# CAN_IF.net
KiCad netlist of a schematic drawn in Altium Designer
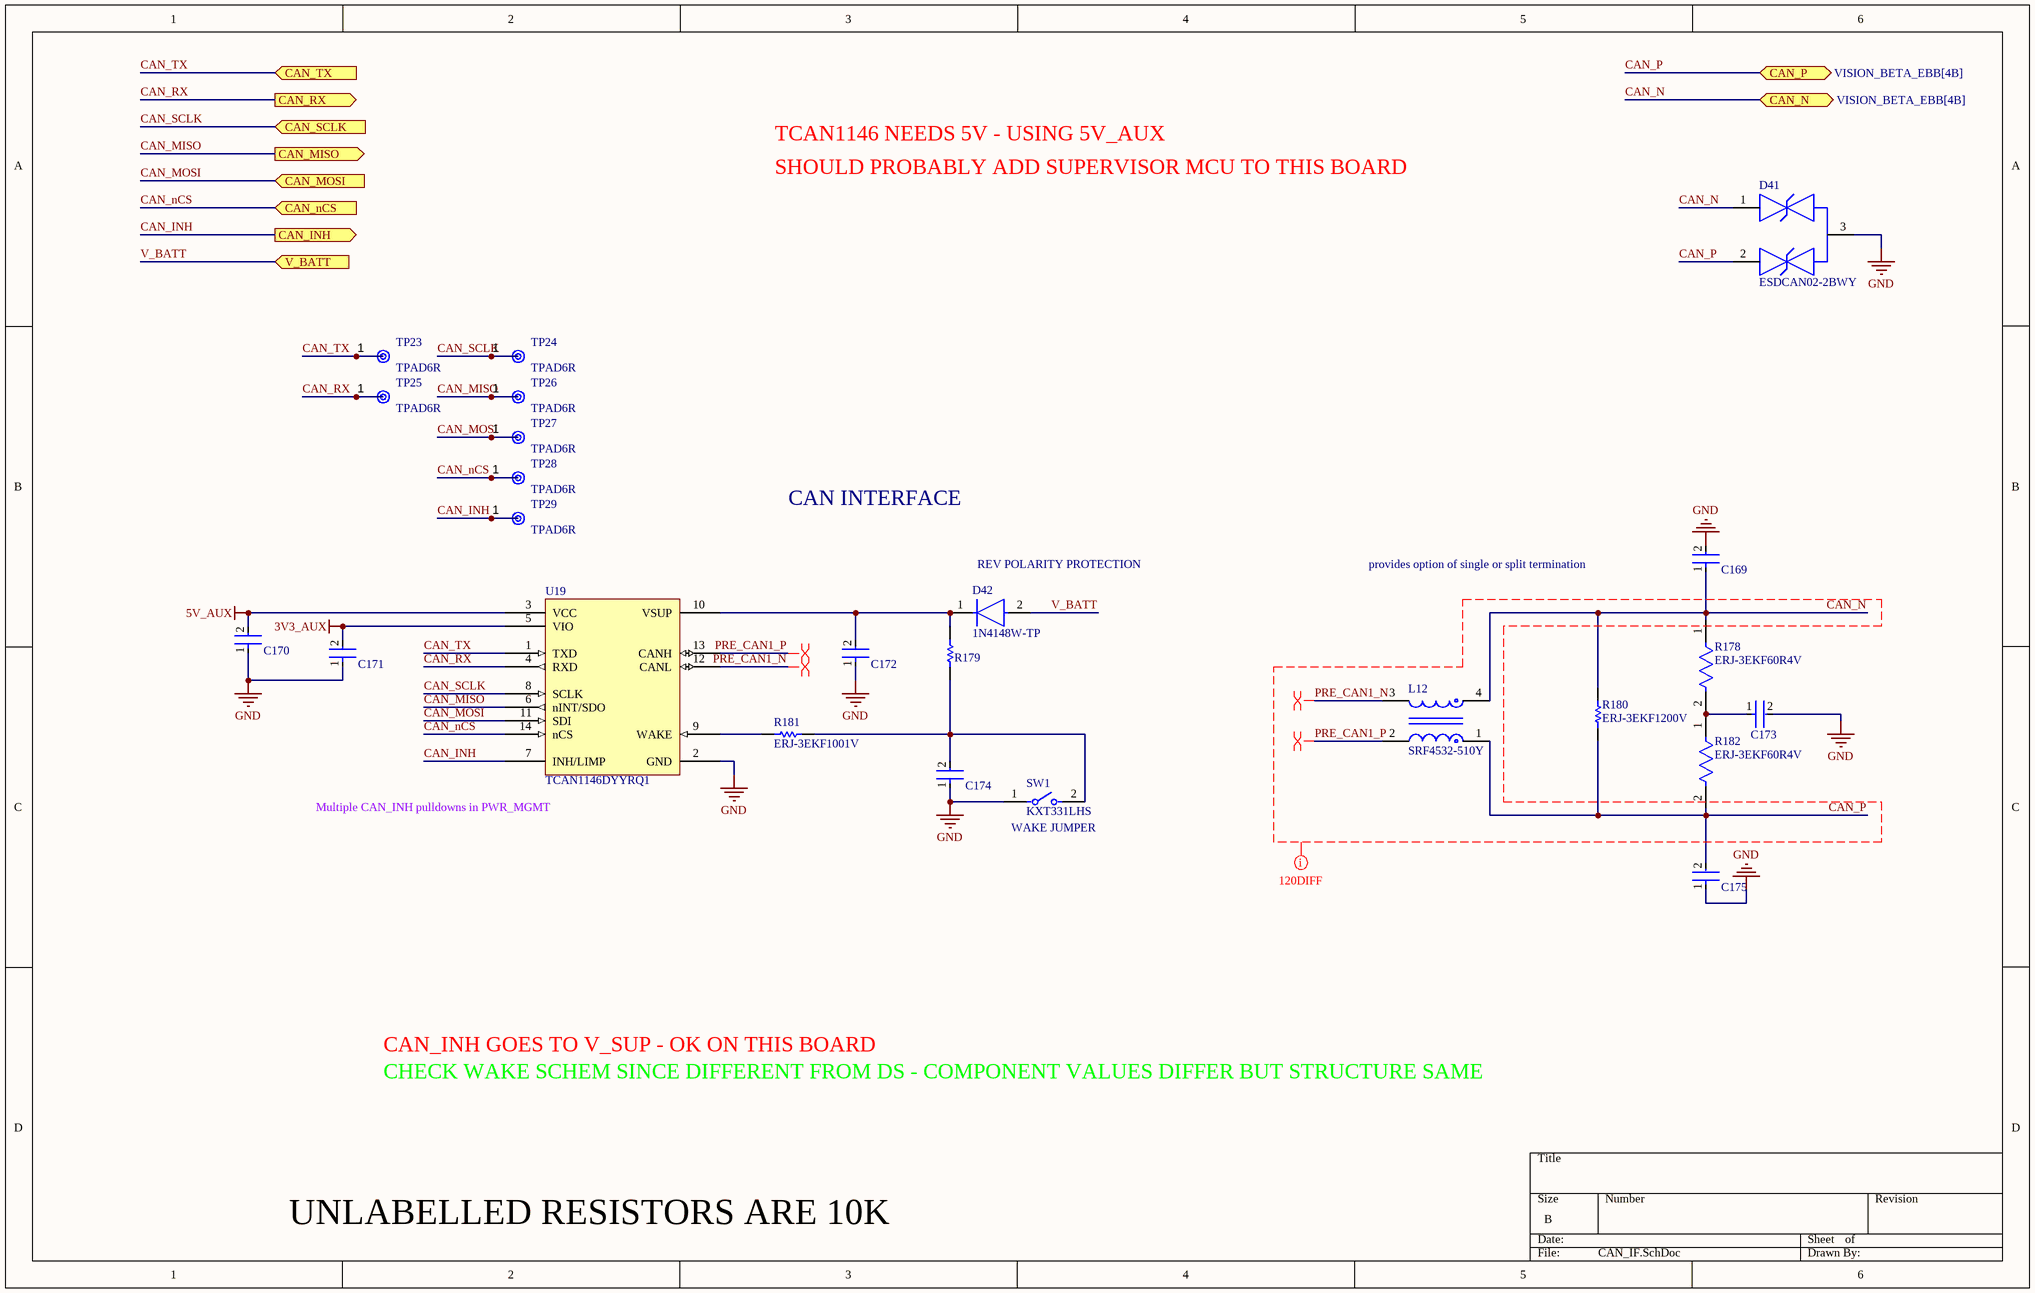
[diagram p0: CAN_IF.SchDoc]

(export (version "E")
  (design (tool "Eeschema 10.0.6"))
  (components
    (comp (ref "C169")
      (value "C0402C104K8PACTU")
      (footprint "FP-C0402-BB-MFG")
      (description "CAP CER 0.1UF 10V X5R 0402")
      (fields (field (name "MANUFACTURER") "Kemet") (field (name "TOLERANCE") "0.1"))
      (libsource (lib "Altium Content Vault") (part "b4654b650e69147ec39a6b967a45e02"))
    )
    (comp (ref "C170")
      (value "C0402C104K8PACTU")
      (footprint "FP-C0402-BB-MFG")
      (description "CAP CER 0.1UF 10V X5R 0402")
      (fields (field (name "MANUFACTURER") "Kemet") (field (name "TOLERANCE") "0.1"))
      (libsource (lib "Altium Content Vault") (part "b4654b650e69147ec39a6b967a45e02"))
    )
    (comp (ref "C171")
      (value "C0402C104K8PACTU")
      (footprint "FP-C0402-BB-MFG")
      (description "CAP CER 0.1UF 10V X5R 0402")
      (fields (field (name "MANUFACTURER") "Kemet") (field (name "TOLERANCE") "0.1"))
      (libsource (lib "Altium Content Vault") (part "b4654b650e69147ec39a6b967a45e02"))
    )
    (comp (ref "C172")
      (value "C0402C104K8PACTU")
      (footprint "FP-C0402-BB-MFG")
      (description "CAP CER 0.1UF 10V X5R 0402")
      (fields (field (name "MANUFACTURER") "Kemet") (field (name "TOLERANCE") "0.1"))
      (libsource (lib "Altium Content Vault") (part "b4654b650e69147ec39a6b967a45e02"))
    )
    (comp (ref "C173")
      (value "C0402C104K8PACTU")
      (footprint "FP-C0402-BB-MFG")
      (description "CAP CER 0.1UF 10V X5R 0402")
      (fields (field (name "MANUFACTURER") "Kemet") (field (name "TOLERANCE") "0.1"))
      (libsource (lib "Altium Content Vault") (part "b4654b650e69147ec39a6b967a45e02"))
    )
    (comp (ref "C174")
      (value "C0402C104K8PACTU")
      (footprint "FP-C0402-BB-MFG")
      (description "CAP CER 0.1UF 10V X5R 0402")
      (fields (field (name "MANUFACTURER") "Kemet") (field (name "TOLERANCE") "0.1"))
      (libsource (lib "Altium Content Vault") (part "b4654b650e69147ec39a6b967a45e02"))
    )
    (comp (ref "C175")
      (value "C0402C104K8PACTU")
      (footprint "FP-C0402-BB-MFG")
      (description "CAP CER 0.1UF 10V X5R 0402")
      (fields (field (name "MANUFACTURER") "Kemet") (field (name "TOLERANCE") "0.1"))
      (libsource (lib "Altium Content Vault") (part "b4654b650e69147ec39a6b967a45e02"))
    )
    (comp (ref "D41")
      (value "ESDCAN02-2BWY")
      (footprint "FP-SOT323-3L-MFG")
      (description "TVS DIODE 26.5V 44V SOT323-3")
      (fields
        (field (name "MANUFACTURER") "STMicroelectronics")
        (field (name "OCTOPART") "https://octopart.com/esdcan02-2bwy-stmicroelectronics-58631133")
      )
      (libsource (lib "Altium Content Vault") (part "0b9019fb5e52ed66df21ec1535be59d"))
    )
    (comp (ref "D42")
      (value "1N4148W-TP")
      (footprint "FP-SOD-123-IPC_A")
      (description "DIODE GEN PURP 100V 150MA SOD123")
      (libsource (lib "Altium Content Vault") (part "d7152d700b627762746794eb795d46e"))
    )
    (comp (ref "L12")
      (value "SRF4532-510Y")
      (footprint "FP-SRF4532-MFG")
      (description "CMC 51UH 200MA 2LN 2KOHM SMD")
      (fields (field (name "TOLERANCE") "50%"))
      (libsource (lib "Altium Content Vault") (part "aca3f6a10b859f211cca95010157f3b"))
    )
    (comp (ref "R178")
      (value "ERJ-3EKF60R4V")
      (footprint "FP-ERJ3EK-IPC_C")
      (description "RES SMD 60.4 OHM 1% 1/10W 0603")
      (fields (field (name "TOLERANCE") "1%"))
      (libsource (lib "Altium Content Vault") (part "1029c3af85768c4190bb7ad29bc67b5"))
    )
    (comp (ref "R179")
      (value "ERJ3EKF1002V")
      (footprint "RESC1609X55X30LL15T15")
      (description "Chip Resistor, 10 KOhm, +/- 1%, 0.1 W, -55 to 155 degC, 0603 (1608 Metric), RoHS, Tape and Reel")
      (fields (field (name "TOLERANCE") "1%") (field (name "MANUFACTURER") "Panasonic"))
      (libsource (lib "Altium Content Vault") (part "RES-2"))
    )
    (comp (ref "R180")
      (value "ERJ-3EKF1200V")
      (footprint "RESC1609X55X30ML15T15")
      (description "Chip Resistor, 120 Ohm, +/- 1%, 0.1 W, -55 to 155 degC, 0603 (1608 Metric), RoHS, Tape and Reel")
      (fields (field (name "TOLERANCE") "1%") (field (name "MANUFACTURER") "Panasonic"))
      (libsource (lib "Altium Content Vault") (part "RES-2"))
    )
    (comp (ref "R181")
      (value "ERJ-3EKF1001V")
      (footprint "RESC1608X55X30LL15T15")
      (fields (field (name "MANUFACTURER") "Panasonic"))
      (libsource (lib "Altium Content Vault") (part "RES"))
    )
    (comp (ref "R182")
      (value "ERJ-3EKF60R4V")
      (footprint "FP-ERJ3EK-IPC_C")
      (description "RES SMD 60.4 OHM 1% 1/10W 0603")
      (fields (field (name "TOLERANCE") "1%"))
      (libsource (lib "Altium Content Vault") (part "1029c3af85768c4190bb7ad29bc67b5"))
    )
    (comp (ref "SW1")
      (value "KXT331LHS")
      (footprint "FP-KXT331LHS-MFG")
      (description "SWITCH TACTILE SPST-NO 0.02A 15V")
      (libsource (lib "Altium Content Vault") (part "bb27bde45df87f1f469753f287ef5ae"))
    )
    (comp (ref "TP23")
      (value "TPAD6R")
      (footprint "New footprint 1")
      (description "Test Point .6mm")
      (libsource (lib "Space Concordia") (part "TP"))
    )
    (comp (ref "TP24")
      (value "TPAD6R")
      (footprint "New footprint 1")
      (description "Test Point .6mm")
      (libsource (lib "Space Concordia") (part "TP"))
    )
    (comp (ref "TP25")
      (value "TPAD6R")
      (footprint "New footprint 1")
      (description "Test Point .6mm")
      (libsource (lib "Space Concordia") (part "TP"))
    )
    (comp (ref "TP26")
      (value "TPAD6R")
      (footprint "New footprint 1")
      (description "Test Point .6mm")
      (libsource (lib "Space Concordia") (part "TP"))
    )
    (comp (ref "TP27")
      (value "TPAD6R")
      (footprint "New footprint 1")
      (description "Test Point .6mm")
      (libsource (lib "Space Concordia") (part "TP"))
    )
    (comp (ref "TP28")
      (value "TPAD6R")
      (footprint "New footprint 1")
      (description "Test Point .6mm")
      (libsource (lib "Space Concordia") (part "TP"))
    )
    (comp (ref "TP29")
      (value "TPAD6R")
      (footprint "New footprint 1")
      (description "Test Point .6mm")
      (libsource (lib "Space Concordia") (part "TP"))
    )
    (comp (ref "U19")
      (value "TCAN1146DYYRQ1")
      (footprint "TCAN1146DYYRQ1-Footprint-1")
      (libsource (lib "Space Concordia") (part "CMP-015-00012-2"))
    )
  )
  (nets
    (net (code "1") (name "/CAN_INH") (class "Default")
      (node (ref "TP29") (pin "1") (pinfunction "TP_1") (pintype "passive"))
      (node (ref "U19") (pin "7") (pinfunction "INH/LIMP_7") (pintype "passive"))
    )
    (net (code "2") (name "/CAN_MISO") (class "Default")
      (node (ref "TP26") (pin "1") (pinfunction "TP_1") (pintype "passive"))
      (node (ref "U19") (pin "6") (pinfunction "nINT/SDO_6") (pintype "output"))
    )
    (net (code "3") (name "/CAN_MOSI") (class "Default")
      (node (ref "TP27") (pin "1") (pinfunction "TP_1") (pintype "passive"))
      (node (ref "U19") (pin "11") (pinfunction "SDI_11") (pintype "input"))
    )
    (net (code "4") (name "/CAN_N") (class "Default")
      (node (ref "C169") (pin "1") (pinfunction "1_1") (pintype "passive"))
      (node (ref "D41") (pin "1") (pinfunction "1_1") (pintype "passive"))
      (node (ref "L12") (pin "4") (pinfunction "4_4") (pintype "passive"))
      (node (ref "R178") (pin "1") (pinfunction "1_1") (pintype "passive"))
      (node (ref "R180") (pin "1") (pinfunction "1_1") (pintype "passive"))
    )
    (net (code "5") (name "/CAN_P") (class "Default")
      (node (ref "C175") (pin "2") (pinfunction "2_2") (pintype "passive"))
      (node (ref "D41") (pin "2") (pinfunction "2_2") (pintype "passive"))
      (node (ref "L12") (pin "1") (pinfunction "1_1") (pintype "passive"))
      (node (ref "R180") (pin "2") (pinfunction "2_2") (pintype "passive"))
      (node (ref "R182") (pin "2") (pinfunction "2_2") (pintype "passive"))
    )
    (net (code "6") (name "/CAN_RX") (class "Default")
      (node (ref "TP25") (pin "1") (pinfunction "TP_1") (pintype "passive"))
      (node (ref "U19") (pin "4") (pinfunction "RXD_4") (pintype "output"))
    )
    (net (code "7") (name "/CAN_SCLK") (class "Default")
      (node (ref "TP24") (pin "1") (pinfunction "TP_1") (pintype "passive"))
      (node (ref "U19") (pin "8") (pinfunction "SCLK_8") (pintype "input"))
    )
    (net (code "8") (name "/CAN_TX") (class "Default")
      (node (ref "TP23") (pin "1") (pinfunction "TP_1") (pintype "passive"))
      (node (ref "U19") (pin "1") (pinfunction "TXD_1") (pintype "input"))
    )
    (net (code "9") (name "/CAN_nCS") (class "Default")
      (node (ref "TP28") (pin "1") (pinfunction "TP_1") (pintype "passive"))
      (node (ref "U19") (pin "14") (pinfunction "nCS_14") (pintype "input"))
    )
    (net (code "10") (name "/PRE_CAN1_N") (class "Default")
      (node (ref "L12") (pin "3") (pinfunction "3_3") (pintype "passive"))
      (node (ref "U19") (pin "12") (pinfunction "CANL_12") (pintype "bidirectional"))
    )
    (net (code "11") (name "/PRE_CAN1_P") (class "Default")
      (node (ref "L12") (pin "2") (pinfunction "2_2") (pintype "passive"))
      (node (ref "U19") (pin "13") (pinfunction "CANH_13") (pintype "bidirectional"))
    )
    (net (code "12") (name "/V_BATT") (class "Default")
      (node (ref "D42") (pin "2") (pinfunction "A_2") (pintype "passive"))
    )
    (net (code "13") (name "3V3_AUX") (class "Default")
      (node (ref "C171") (pin "2") (pinfunction "2_2") (pintype "passive"))
      (node (ref "U19") (pin "5") (pinfunction "VIO_5") (pintype "power_in"))
    )
    (net (code "14") (name "5V_AUX") (class "Default")
      (node (ref "C170") (pin "2") (pinfunction "2_2") (pintype "passive"))
      (node (ref "U19") (pin "3") (pinfunction "VCC_3") (pintype "power_in"))
    )
    (net (code "15") (name "GND") (class "Default")
      (node (ref "C169") (pin "2") (pinfunction "2_2") (pintype "passive"))
      (node (ref "C170") (pin "1") (pinfunction "1_1") (pintype "passive"))
      (node (ref "C171") (pin "1") (pinfunction "1_1") (pintype "passive"))
      (node (ref "C172") (pin "1") (pinfunction "1_1") (pintype "passive"))
      (node (ref "C173") (pin "2") (pinfunction "2_2") (pintype "passive"))
      (node (ref "C174") (pin "1") (pinfunction "1_1") (pintype "passive"))
      (node (ref "C175") (pin "1") (pinfunction "1_1") (pintype "passive"))
      (node (ref "D41") (pin "3") (pinfunction "3_3") (pintype "passive"))
      (node (ref "SW1") (pin "1") (pinfunction "1_1") (pintype "passive"))
      (node (ref "U19") (pin "2") (pinfunction "GND_2") (pintype "power_in"))
    )
    (net (code "16") (name "Net-(C173-Pad1)") (class "Default")
      (node (ref "C173") (pin "1") (pinfunction "1_1") (pintype "passive"))
      (node (ref "R178") (pin "2") (pinfunction "2_2") (pintype "passive"))
      (node (ref "R182") (pin "1") (pinfunction "1_1") (pintype "passive"))
    )
    (net (code "17") (name "Net-(C174-Pad2)") (class "Default")
      (node (ref "C174") (pin "2") (pinfunction "2_2") (pintype "passive"))
      (node (ref "R179") (pin "2") (pinfunction "2_2") (pintype "passive"))
      (node (ref "R181") (pin "2") (pinfunction "2_2") (pintype "passive"))
      (node (ref "SW1") (pin "2") (pinfunction "2_2") (pintype "passive"))
    )
    (net (code "18") (name "Net-(D42-C)") (class "Default")
      (node (ref "C172") (pin "2") (pinfunction "2_2") (pintype "passive"))
      (node (ref "D42") (pin "1") (pinfunction "C_1") (pintype "passive"))
      (node (ref "R179") (pin "1") (pinfunction "1_1") (pintype "passive"))
      (node (ref "U19") (pin "10") (pinfunction "VSUP_10") (pintype "power_in"))
    )
    (net (code "19") (name "Net-(U19-WAKE)") (class "Default")
      (node (ref "R181") (pin "1") (pinfunction "1_1") (pintype "passive"))
      (node (ref "U19") (pin "9") (pinfunction "WAKE_9") (pintype "input"))
    )
  )
)
